# W076B.net
KiCad netlist of a schematic drawn in EAGLE
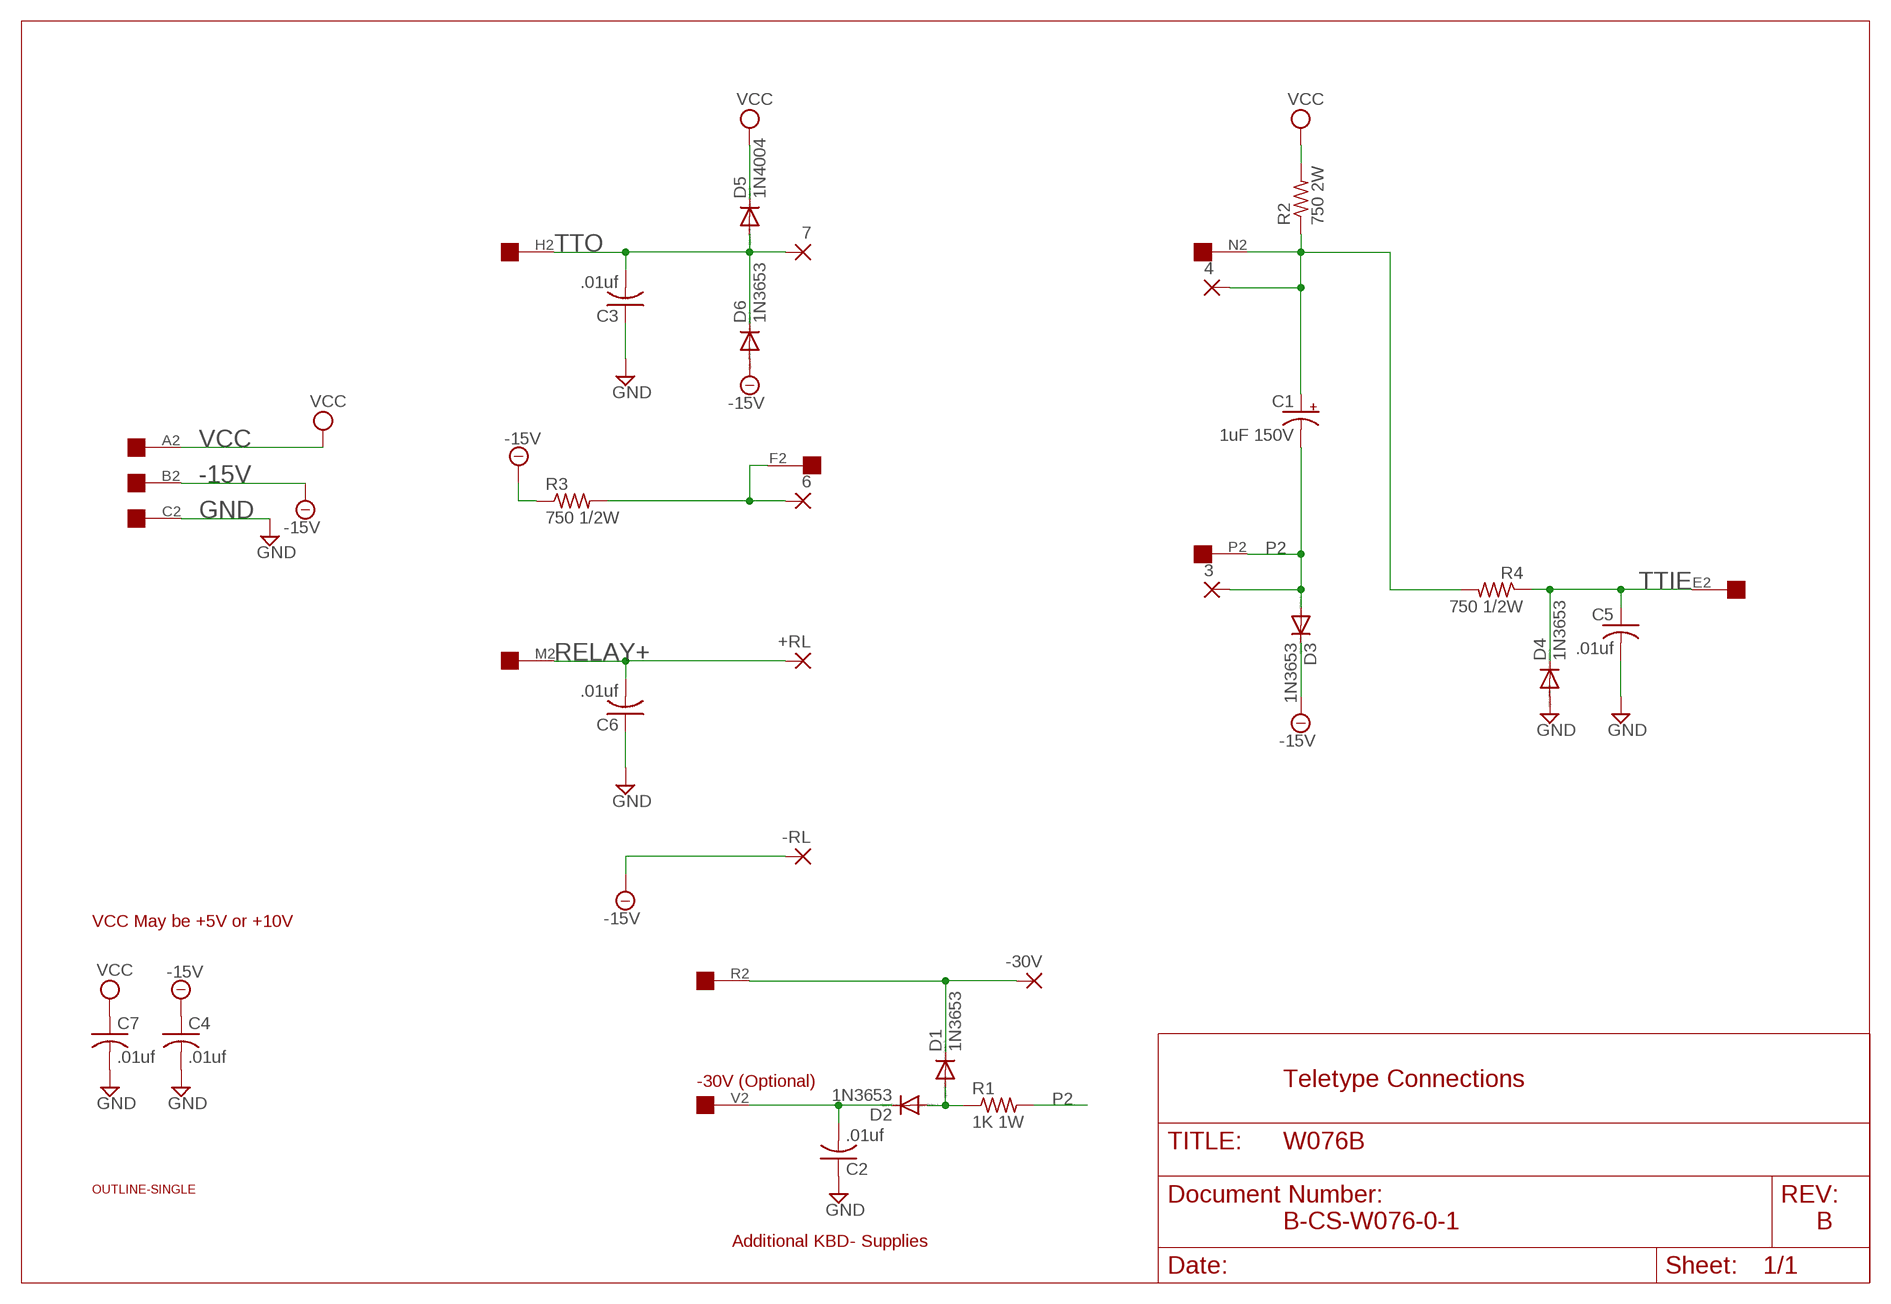
[diagram p0: schematic, sheet 1]

(export (version "E")
  (design (tool "Eeschema 10.0.6"))
  (components
    (comp (ref "+RL")
      (value "2,54/1,0")
      (footprint "eagle-import:2,54_1,0")
      (libsource (lib "eagle-import") (part "2,54/1,0"))
    )
    (comp (ref "-30V")
      (value "2,54/1,0")
      (footprint "eagle-import:2,54_1,0")
      (libsource (lib "eagle-import") (part "2,54/1,0"))
    )
    (comp (ref "-RL")
      (value "2,54/1,0")
      (footprint "eagle-import:2,54_1,0")
      (libsource (lib "eagle-import") (part "2,54/1,0"))
    )
    (comp (ref "3")
      (value "2,54/1,0")
      (footprint "eagle-import:2,54_1,0")
      (libsource (lib "eagle-import") (part "2,54/1,0"))
    )
    (comp (ref "4")
      (value "2,54/1,0")
      (footprint "eagle-import:2,54_1,0")
      (libsource (lib "eagle-import") (part "2,54/1,0"))
    )
    (comp (ref "6")
      (value "2,54/1,0")
      (footprint "eagle-import:2,54_1,0")
      (libsource (lib "eagle-import") (part "2,54/1,0"))
    )
    (comp (ref "7")
      (value "2,54/1,0")
      (footprint "eagle-import:2,54_1,0")
      (libsource (lib "eagle-import") (part "2,54/1,0"))
    )
    (comp (ref "C1")
      (value "1uF 150V")
      (footprint "eagle-import:E25-9")
      (libsource (lib "eagle-import") (part "CPOL-USE25-9AXIAL"))
    )
    (comp (ref "C2")
      (value ".01uf")
      (footprint "eagle-import:C050-025X075")
      (libsource (lib "eagle-import") (part "C-US050-025X075"))
    )
    (comp (ref "C3")
      (value ".01uf")
      (footprint "eagle-import:C050-025X075")
      (libsource (lib "eagle-import") (part "C-US050-025X075"))
    )
    (comp (ref "C4")
      (value ".01uf")
      (footprint "eagle-import:C050-025X075")
      (libsource (lib "eagle-import") (part "C-US050-025X075"))
    )
    (comp (ref "C5")
      (value ".01uf")
      (footprint "eagle-import:C050-025X075")
      (libsource (lib "eagle-import") (part "C-US050-025X075"))
    )
    (comp (ref "C6")
      (value ".01uf")
      (footprint "eagle-import:C050-025X075")
      (libsource (lib "eagle-import") (part "C-US050-025X075"))
    )
    (comp (ref "C7")
      (value ".01uf")
      (footprint "eagle-import:C050-025X075")
      (libsource (lib "eagle-import") (part "C-US050-025X075"))
    )
    (comp (ref "D1")
      (value "1N3653")
      (footprint "eagle-import:DO35-10")
      (libsource (lib "eagle-import") (part "1N4148DO35-10"))
    )
    (comp (ref "D2")
      (value "1N3653")
      (footprint "eagle-import:DO35-10")
      (libsource (lib "eagle-import") (part "1N4148DO35-10"))
    )
    (comp (ref "D3")
      (value "1N3653")
      (footprint "eagle-import:DO35-10")
      (libsource (lib "eagle-import") (part "1N4148DO35-10"))
    )
    (comp (ref "D4")
      (value "1N3653")
      (footprint "eagle-import:DO35-10")
      (libsource (lib "eagle-import") (part "1N4148DO35-10"))
    )
    (comp (ref "D5")
      (value "1N4004")
      (footprint "eagle-import:DO35-10")
      (libsource (lib "eagle-import") (part "1N4148DO35-10"))
    )
    (comp (ref "D6")
      (value "1N3653")
      (footprint "eagle-import:DO35-10")
      (libsource (lib "eagle-import") (part "1N4148DO35-10"))
    )
    (comp (ref "EDGE")
      (value "EDGE-1")
      (footprint "eagle-import:EDGE-CON1")
      (libsource (lib "eagle-import") (part "EDGE-1"))
    )
    (comp (ref "R1")
      (value "1K 1W")
      (footprint "eagle-import:0617_22")
      (libsource (lib "eagle-import") (part "R-US_0617/22"))
    )
    (comp (ref "R2")
      (value "750 2W")
      (footprint "eagle-import:P0817_22")
      (libsource (lib "eagle-import") (part "R-US_0817/22"))
    )
    (comp (ref "R3")
      (value "750 1/2W")
      (footprint "eagle-import:0411_15")
      (libsource (lib "eagle-import") (part "R-US_0411/15"))
    )
    (comp (ref "R4")
      (value "750 1/2W")
      (footprint "eagle-import:0411_15")
      (libsource (lib "eagle-import") (part "R-US_0411/15"))
    )
    (comp (ref "U$1")
      (value "OUTLINE-SINGLE")
      (footprint "eagle-import:SINGLE")
      (libsource (lib "eagle-import") (part "OUTLINE-SINGLE"))
    )
  )
  (nets
    (net (code "1") (name "-15V") (class "Default")
      (node (ref "-RL") (pin "1") (pinfunction "P_1") (pintype "passive"))
      (node (ref "C4") (pin "1") (pinfunction "1_1") (pintype "passive"))
      (node (ref "D3") (pin "C") (pinfunction "C_C") (pintype "passive"))
      (node (ref "D6") (pin "A") (pinfunction "A_A") (pintype "passive"))
      (node (ref "EDGE") (pin "B2") (pinfunction "1_B2") (pintype "bidirectional"))
      (node (ref "R3") (pin "1") (pinfunction "1_1") (pintype "passive"))
    )
    (net (code "2") (name "/P2") (class "Default")
      (node (ref "3") (pin "1") (pinfunction "P_1") (pintype "passive"))
      (node (ref "C1") (pin "-") (pinfunction "-_-") (pintype "passive"))
      (node (ref "D3") (pin "A") (pinfunction "A_A") (pintype "passive"))
      (node (ref "EDGE") (pin "P2") (pinfunction "1_P2") (pintype "bidirectional"))
      (node (ref "R1") (pin "2") (pinfunction "2_2") (pintype "passive"))
    )
    (net (code "3") (name "/RELAY+") (class "Default")
      (node (ref "+RL") (pin "1") (pinfunction "P_1") (pintype "passive"))
      (node (ref "C6") (pin "2") (pinfunction "2_2") (pintype "passive"))
      (node (ref "EDGE") (pin "M2") (pinfunction "1_M2") (pintype "bidirectional"))
    )
    (net (code "4") (name "/TTIE") (class "Default")
      (node (ref "C5") (pin "1") (pinfunction "1_1") (pintype "passive"))
      (node (ref "D4") (pin "C") (pinfunction "C_C") (pintype "passive"))
      (node (ref "EDGE") (pin "E2") (pinfunction "1_E2") (pintype "bidirectional"))
      (node (ref "R4") (pin "1") (pinfunction "1_1") (pintype "passive"))
    )
    (net (code "5") (name "/TTO") (class "Default")
      (node (ref "7") (pin "1") (pinfunction "P_1") (pintype "passive"))
      (node (ref "C3") (pin "2") (pinfunction "2_2") (pintype "passive"))
      (node (ref "D5") (pin "A") (pinfunction "A_A") (pintype "passive"))
      (node (ref "D6") (pin "C") (pinfunction "C_C") (pintype "passive"))
      (node (ref "EDGE") (pin "H2") (pinfunction "1_H2") (pintype "bidirectional"))
    )
    (net (code "6") (name "GND") (class "Default")
      (node (ref "C2") (pin "1") (pinfunction "1_1") (pintype "passive"))
      (node (ref "C3") (pin "1") (pinfunction "1_1") (pintype "passive"))
      (node (ref "C4") (pin "2") (pinfunction "2_2") (pintype "passive"))
      (node (ref "C5") (pin "2") (pinfunction "2_2") (pintype "passive"))
      (node (ref "C6") (pin "1") (pinfunction "1_1") (pintype "passive"))
      (node (ref "C7") (pin "2") (pinfunction "2_2") (pintype "passive"))
      (node (ref "D4") (pin "A") (pinfunction "A_A") (pintype "passive"))
      (node (ref "EDGE") (pin "C2") (pinfunction "1_C2") (pintype "bidirectional"))
    )
    (net (code "7") (name "Net-(-30V-P)") (class "Default")
      (node (ref "-30V") (pin "1") (pinfunction "P_1") (pintype "passive"))
      (node (ref "D1") (pin "C") (pinfunction "C_C") (pintype "passive"))
      (node (ref "EDGE") (pin "R2") (pinfunction "1_R2") (pintype "bidirectional"))
    )
    (net (code "8") (name "Net-(4-P)") (class "Default")
      (node (ref "4") (pin "1") (pinfunction "P_1") (pintype "passive"))
      (node (ref "C1") (pin "+") (pinfunction "+_+") (pintype "passive"))
      (node (ref "EDGE") (pin "N2") (pinfunction "1_N2") (pintype "bidirectional"))
      (node (ref "R2") (pin "1") (pinfunction "1_1") (pintype "passive"))
      (node (ref "R4") (pin "2") (pinfunction "2_2") (pintype "passive"))
    )
    (net (code "9") (name "Net-(6-P)") (class "Default")
      (node (ref "6") (pin "1") (pinfunction "P_1") (pintype "passive"))
      (node (ref "EDGE") (pin "F2") (pinfunction "1_F2") (pintype "bidirectional"))
      (node (ref "R3") (pin "2") (pinfunction "2_2") (pintype "passive"))
    )
    (net (code "10") (name "Net-(D1-PadA)") (class "Default")
      (node (ref "D1") (pin "A") (pinfunction "A_A") (pintype "passive"))
      (node (ref "D2") (pin "A") (pinfunction "A_A") (pintype "passive"))
      (node (ref "R1") (pin "1") (pinfunction "1_1") (pintype "passive"))
    )
    (net (code "11") (name "Net-(EDGER-1)") (class "Default")
      (node (ref "C2") (pin "2") (pinfunction "2_2") (pintype "passive"))
      (node (ref "D2") (pin "C") (pinfunction "C_C") (pintype "passive"))
      (node (ref "EDGE") (pin "V2") (pinfunction "1_V2") (pintype "bidirectional"))
    )
    (net (code "12") (name "VCC") (class "Default")
      (node (ref "C7") (pin "1") (pinfunction "1_1") (pintype "passive"))
      (node (ref "D5") (pin "C") (pinfunction "C_C") (pintype "passive"))
      (node (ref "EDGE") (pin "A2") (pinfunction "1_A2") (pintype "bidirectional"))
      (node (ref "R2") (pin "2") (pinfunction "2_2") (pintype "passive"))
    )
  )
)
